# Player.net
KiCad netlist of a schematic drawn in EAGLE
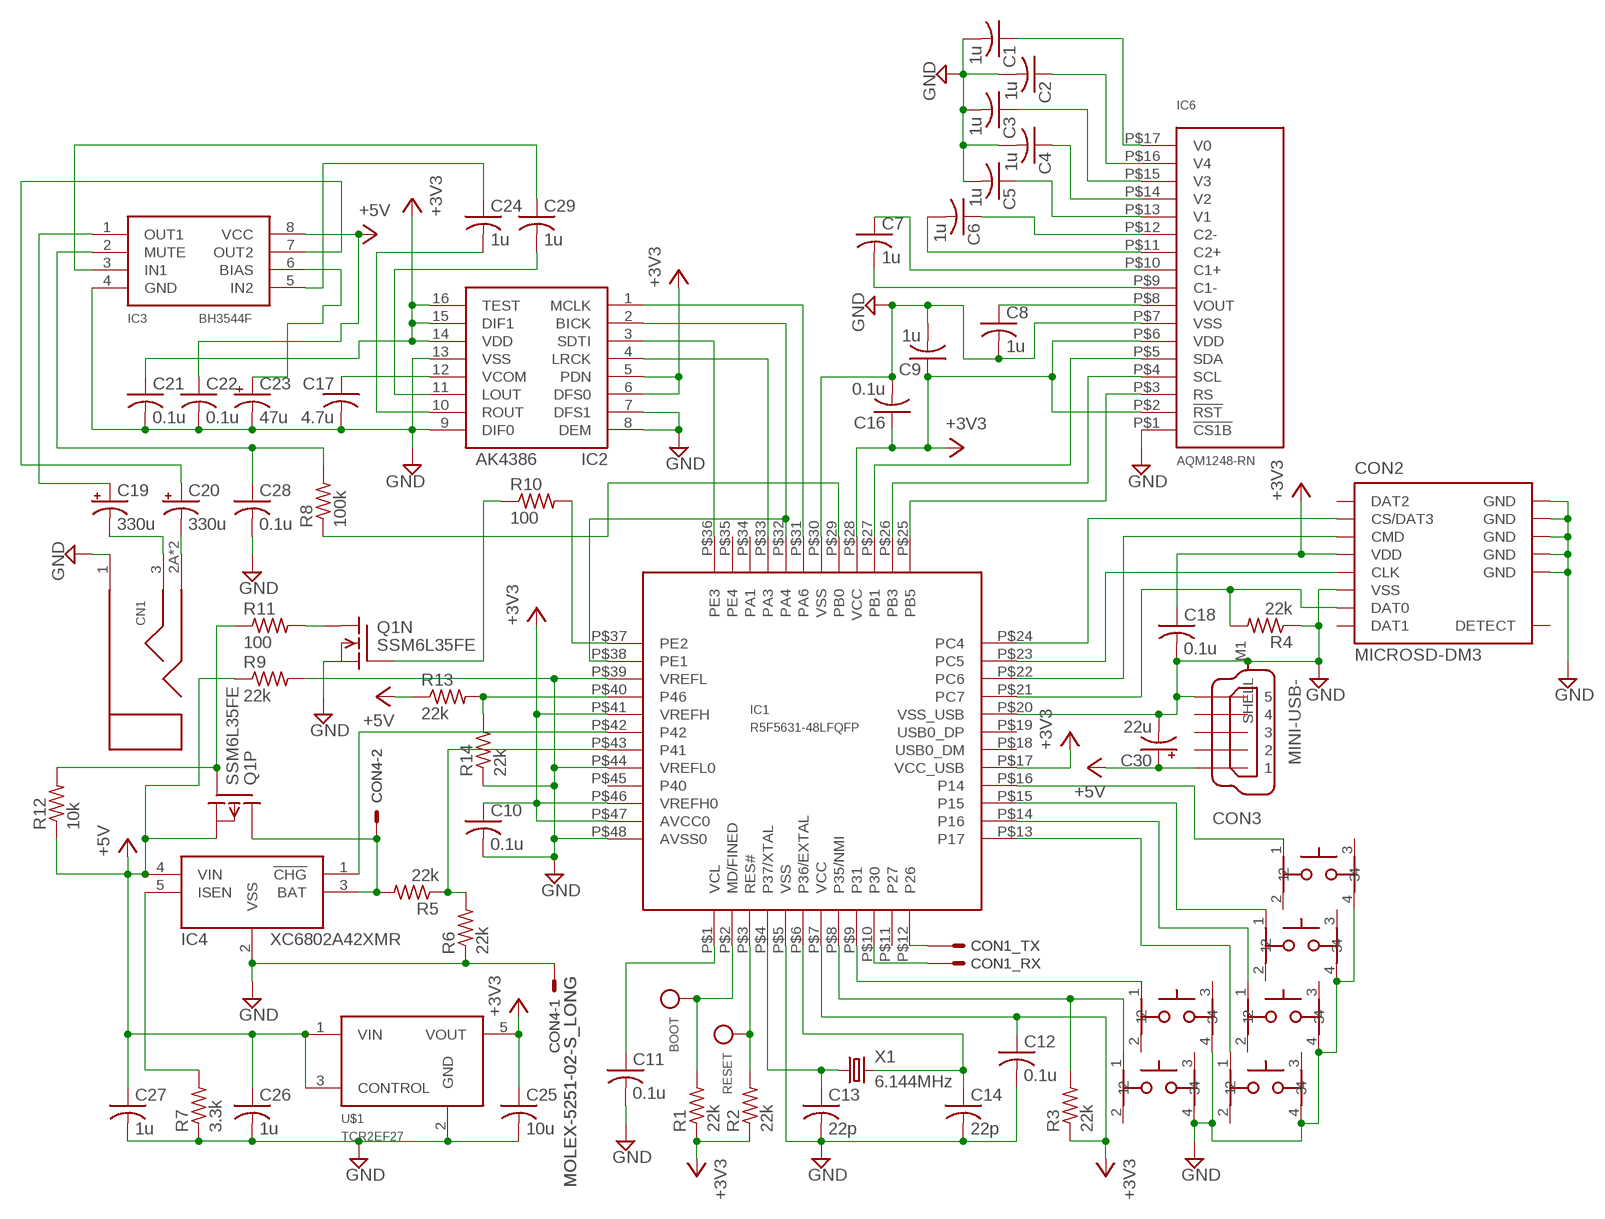
[diagram p0: schematic, sheet 1]

(export (version "E")
  (design (tool "Eeschema 10.0.6"))
  (components
    (comp (ref "BOOT")
      (value "CHECK_PIN")
      (footprint "eagle-import:SLC-22-G")
      (libsource (lib "eagle-import") (part "CHECK_PIN"))
    )
    (comp (ref "C1")
      (value "1u")
      (footprint "eagle-import:2012-C")
      (libsource (lib "eagle-import") (part "C-2012"))
    )
    (comp (ref "C2")
      (value "1u")
      (footprint "eagle-import:2012-C")
      (libsource (lib "eagle-import") (part "C-2012"))
    )
    (comp (ref "C3")
      (value "1u")
      (footprint "eagle-import:2012-C")
      (libsource (lib "eagle-import") (part "C-2012"))
    )
    (comp (ref "C4")
      (value "1u")
      (footprint "eagle-import:2012-C")
      (libsource (lib "eagle-import") (part "C-2012"))
    )
    (comp (ref "C5")
      (value "1u")
      (footprint "eagle-import:2012-C")
      (libsource (lib "eagle-import") (part "C-2012"))
    )
    (comp (ref "C6")
      (value "1u")
      (footprint "eagle-import:2012-C")
      (libsource (lib "eagle-import") (part "C-2012"))
    )
    (comp (ref "C7")
      (value "1u")
      (footprint "eagle-import:2012-C")
      (libsource (lib "eagle-import") (part "C-2012"))
    )
    (comp (ref "C8")
      (value "1u")
      (footprint "eagle-import:2012-C")
      (libsource (lib "eagle-import") (part "C-2012"))
    )
    (comp (ref "C9")
      (value "1u")
      (footprint "eagle-import:2012-C")
      (libsource (lib "eagle-import") (part "C-2012"))
    )
    (comp (ref "C10")
      (value "0.1u")
      (footprint "eagle-import:2012-C")
      (libsource (lib "eagle-import") (part "C-2012"))
    )
    (comp (ref "C11")
      (value "0.1u")
      (footprint "eagle-import:2012-C")
      (libsource (lib "eagle-import") (part "C-2012"))
    )
    (comp (ref "C12")
      (value "0.1u")
      (footprint "eagle-import:2012-C")
      (libsource (lib "eagle-import") (part "C-2012"))
    )
    (comp (ref "C13")
      (value "22p")
      (footprint "eagle-import:1608")
      (libsource (lib "eagle-import") (part "C-1608"))
    )
    (comp (ref "C14")
      (value "22p")
      (footprint "eagle-import:1608")
      (libsource (lib "eagle-import") (part "C-1608"))
    )
    (comp (ref "C16")
      (value "0.1u")
      (footprint "eagle-import:2012-C")
      (libsource (lib "eagle-import") (part "C-2012"))
    )
    (comp (ref "C17")
      (value "4.7u")
      (footprint "eagle-import:2012-C")
      (libsource (lib "eagle-import") (part "C-2012"))
    )
    (comp (ref "C18")
      (value "0.1u")
      (footprint "eagle-import:2012-C")
      (libsource (lib "eagle-import") (part "C-2012"))
    )
    (comp (ref "C19")
      (value "330u")
      (footprint "eagle-import:E2,5-8")
      (libsource (lib "eagle-import") (part "CC-2.5-8"))
    )
    (comp (ref "C20")
      (value "330u")
      (footprint "eagle-import:E2,5-8")
      (libsource (lib "eagle-import") (part "CC-2.5-8"))
    )
    (comp (ref "C21")
      (value "0.1u")
      (footprint "eagle-import:2012-C")
      (libsource (lib "eagle-import") (part "C-2012"))
    )
    (comp (ref "C22")
      (value "0.1u")
      (footprint "eagle-import:2012-C")
      (libsource (lib "eagle-import") (part "C-2012"))
    )
    (comp (ref "C23")
      (value "47u")
      (footprint "eagle-import:E2,5-8")
      (libsource (lib "eagle-import") (part "CC-2.5-8"))
    )
    (comp (ref "C24")
      (value "1u")
      (footprint "eagle-import:2012-C")
      (libsource (lib "eagle-import") (part "C-2012"))
    )
    (comp (ref "C25")
      (value "10u")
      (footprint "eagle-import:3216")
      (libsource (lib "eagle-import") (part "C-3216"))
    )
    (comp (ref "C26")
      (value "1u")
      (footprint "eagle-import:2012-C")
      (libsource (lib "eagle-import") (part "C-2012"))
    )
    (comp (ref "C27")
      (value "1u")
      (footprint "eagle-import:2012-C")
      (libsource (lib "eagle-import") (part "C-2012"))
    )
    (comp (ref "C28")
      (value "0.1u")
      (footprint "eagle-import:2012-C")
      (libsource (lib "eagle-import") (part "C-2012"))
    )
    (comp (ref "C29")
      (value "1u")
      (footprint "eagle-import:2012-C")
      (libsource (lib "eagle-import") (part "C-2012"))
    )
    (comp (ref "C30")
      (value "22u")
      (footprint "eagle-import:E2,5-8")
      (libsource (lib "eagle-import") (part "CC-2.5-8"))
    )
    (comp (ref "CN1")
      (value "STEREO-3.5-MJ8435")
      (footprint "eagle-import:MJ8435")
      (libsource (lib "eagle-import") (part "STEREO-3.5-MJ8435"))
    )
    (comp (ref "CON1")
      (value "UART-S")
      (footprint "eagle-import:IL-G-04-S")
      (libsource (lib "eagle-import") (part "UART-S"))
    )
    (comp (ref "CON2")
      (value "MICROSD-DM3")
      (footprint "eagle-import:DM3AT-SF-PEJ")
      (libsource (lib "eagle-import") (part "MICROSD-DM3"))
    )
    (comp (ref "CON3")
      (value "MINI-USB-")
      (footprint "eagle-import:UX60A-MB-5ST")
      (libsource (lib "eagle-import") (part "MINI-USB-"))
    )
    (comp (ref "CON4")
      (value "MOLEX-5251-02-S_LONG")
      (footprint "eagle-import:5251-02-S_LONG")
      (libsource (lib "eagle-import") (part "MOLEX-5251-02-S_LONG"))
    )
    (comp (ref "IC1")
      (value "R5F5631-48LFQFP")
      (footprint "eagle-import:P-LFQFP48-7X7-0.50")
      (libsource (lib "eagle-import") (part "R5F5631-48LFQFP"))
    )
    (comp (ref "IC2")
      (value "AK4386")
      (footprint "eagle-import:TSSOP16")
      (libsource (lib "eagle-import") (part "AK4386"))
    )
    (comp (ref "IC3")
      (value "BH3544F")
      (footprint "eagle-import:SOIC8")
      (libsource (lib "eagle-import") (part "BH3544F"))
    )
    (comp (ref "IC4")
      (value "XC6802A42XMR")
      (footprint "eagle-import:SOT23-5")
      (libsource (lib "eagle-import") (part "XC6802A42XMR"))
    )
    (comp (ref "IC6")
      (value "AQM1248-RN")
      (footprint "eagle-import:AQM1248A-RN")
      (libsource (lib "eagle-import") (part "AQM1248-RN"))
    )
    (comp (ref "Q1")
      (value "SSM6L35FE")
      (footprint "eagle-import:2-2N1D")
      (libsource (lib "eagle-import") (part "SSM6L35FE"))
    )
    (comp (ref "R1")
      (value "22k")
      (footprint "eagle-import:2012-R")
      (libsource (lib "eagle-import") (part "R-2012"))
    )
    (comp (ref "R2")
      (value "22k")
      (footprint "eagle-import:2012-R")
      (libsource (lib "eagle-import") (part "R-2012"))
    )
    (comp (ref "R3")
      (value "22k")
      (footprint "eagle-import:2012-R")
      (libsource (lib "eagle-import") (part "R-2012"))
    )
    (comp (ref "R4")
      (value "22k")
      (footprint "eagle-import:2012-R")
      (libsource (lib "eagle-import") (part "R-2012"))
    )
    (comp (ref "R5")
      (value "22k")
      (footprint "eagle-import:2012-R")
      (libsource (lib "eagle-import") (part "R-2012"))
    )
    (comp (ref "R6")
      (value "22k")
      (footprint "eagle-import:2012-R")
      (libsource (lib "eagle-import") (part "R-2012"))
    )
    (comp (ref "R7")
      (value "3.3k")
      (footprint "eagle-import:2012-R")
      (libsource (lib "eagle-import") (part "R-2012"))
    )
    (comp (ref "R8")
      (value "100k")
      (footprint "eagle-import:2012-R")
      (libsource (lib "eagle-import") (part "R-2012"))
    )
    (comp (ref "R9")
      (value "22k")
      (footprint "eagle-import:2012-R")
      (libsource (lib "eagle-import") (part "R-2012"))
    )
    (comp (ref "R10")
      (value "100")
      (footprint "eagle-import:2012-R")
      (libsource (lib "eagle-import") (part "R-2012"))
    )
    (comp (ref "R11")
      (value "100")
      (footprint "eagle-import:2012-R")
      (libsource (lib "eagle-import") (part "R-2012"))
    )
    (comp (ref "R12")
      (value "10k")
      (footprint "eagle-import:2012-R")
      (libsource (lib "eagle-import") (part "R-2012"))
    )
    (comp (ref "R13")
      (value "22k")
      (footprint "eagle-import:2012-R")
      (libsource (lib "eagle-import") (part "R-2012"))
    )
    (comp (ref "R14")
      (value "22k")
      (footprint "eagle-import:2012-R")
      (libsource (lib "eagle-import") (part "R-2012"))
    )
    (comp (ref "RESET")
      (value "CHECK_PIN")
      (footprint "eagle-import:SLC-22-G")
      (libsource (lib "eagle-import") (part "CHECK_PIN"))
    )
    (comp (ref "SW1")
      (value "PUSHSW")
      (footprint "eagle-import:PUSHSW")
      (libsource (lib "eagle-import") (part "PUSHSW"))
    )
    (comp (ref "SW2")
      (value "PUSHSW")
      (footprint "eagle-import:PUSHSW")
      (libsource (lib "eagle-import") (part "PUSHSW"))
    )
    (comp (ref "SW3")
      (value "PUSHSW")
      (footprint "eagle-import:PUSHSW")
      (libsource (lib "eagle-import") (part "PUSHSW"))
    )
    (comp (ref "SW4")
      (value "PUSHSW")
      (footprint "eagle-import:PUSHSW")
      (libsource (lib "eagle-import") (part "PUSHSW"))
    )
    (comp (ref "SW5")
      (value "PUSHSW")
      (footprint "eagle-import:PUSHSW")
      (libsource (lib "eagle-import") (part "PUSHSW"))
    )
    (comp (ref "SW6")
      (value "PUSHSW")
      (footprint "eagle-import:PUSHSW")
      (libsource (lib "eagle-import") (part "PUSHSW"))
    )
    (comp (ref "U$1")
      (value "TCR2EF27")
      (footprint "eagle-import:5-LEAD_TSOT")
      (libsource (lib "eagle-import") (part "TCR2EF"))
    )
    (comp (ref "X1")
      (value "6.144MHz")
      (footprint "eagle-import:TINYCRYSTAL")
      (libsource (lib "eagle-import") (part "CRYSTALTINY"))
    )
  )
  (nets
    (net (code "1") (name "+3V3") (class "Default")
      (node (ref "C10") (pin "1") (pinfunction "1_1") (pintype "passive"))
      (node (ref "C12") (pin "1") (pinfunction "1_1") (pintype "passive"))
      (node (ref "C16") (pin "1") (pinfunction "1_1") (pintype "passive"))
      (node (ref "C18") (pin "1") (pinfunction "1_1") (pintype "passive"))
      (node (ref "C21") (pin "1") (pinfunction "1_1") (pintype "passive"))
      (node (ref "C25") (pin "1") (pinfunction "1_1") (pintype "passive"))
      (node (ref "C9") (pin "1") (pinfunction "1_1") (pintype "passive"))
      (node (ref "CON2") (pin "4") (pinfunction "VDD_4") (pintype "power_in"))
      (node (ref "IC1") (pin "P$17") (pinfunction "VCC_USB_P$17") (pintype "power_in"))
      (node (ref "IC1") (pin "P$28") (pinfunction "VCC_P$28") (pintype "power_in"))
      (node (ref "IC1") (pin "P$41") (pinfunction "VREFH_P$41") (pintype "passive"))
      (node (ref "IC1") (pin "P$46") (pinfunction "VREFH0_P$46") (pintype "passive"))
      (node (ref "IC1") (pin "P$47") (pinfunction "AVCC0_P$47") (pintype "power_in"))
      (node (ref "IC1") (pin "P$7") (pinfunction "VCC_P$7") (pintype "power_in"))
      (node (ref "IC2") (pin "14") (pinfunction "VDD_14") (pintype "bidirectional"))
      (node (ref "IC2") (pin "15") (pinfunction "DIF1_15") (pintype "bidirectional"))
      (node (ref "IC2") (pin "16") (pinfunction "TEST_16") (pintype "bidirectional"))
      (node (ref "IC2") (pin "5") (pinfunction "PDN_5") (pintype "bidirectional"))
      (node (ref "IC2") (pin "6") (pinfunction "DFS0_6") (pintype "bidirectional"))
      (node (ref "IC6") (pin "P$2") (pinfunction "~{RST}_P$2") (pintype "bidirectional"))
      (node (ref "IC6") (pin "P$6") (pinfunction "VDD_P$6") (pintype "bidirectional"))
      (node (ref "R1") (pin "1") (pinfunction "1_1") (pintype "passive"))
      (node (ref "R2") (pin "1") (pinfunction "1_1") (pintype "passive"))
      (node (ref "R3") (pin "1") (pinfunction "1_1") (pintype "passive"))
      (node (ref "U$1") (pin "5") (pinfunction "VOUT_5") (pintype "bidirectional"))
    )
    (net (code "2") (name "+5V") (class "Default")
      (node (ref "C22") (pin "1") (pinfunction "1_1") (pintype "passive"))
      (node (ref "C26") (pin "1") (pinfunction "1_1") (pintype "passive"))
      (node (ref "C27") (pin "1") (pinfunction "1_1") (pintype "passive"))
      (node (ref "C30") (pin "+") (pinfunction "+_+") (pintype "passive"))
      (node (ref "CON3") (pin "1") (pinfunction "1_1") (pintype "input"))
      (node (ref "IC3") (pin "8") (pinfunction "VCC_8") (pintype "bidirectional"))
      (node (ref "IC4") (pin "4") (pinfunction "VIN_4") (pintype "power_in"))
      (node (ref "Q1") (pin "4") (pinfunction "S_4") (pintype "passive"))
      (node (ref "R12") (pin "1") (pinfunction "1_1") (pintype "passive"))
      (node (ref "R13") (pin "1") (pinfunction "1_1") (pintype "passive"))
      (node (ref "R9") (pin "1") (pinfunction "1_1") (pintype "passive"))
      (node (ref "U$1") (pin "1") (pinfunction "VIN_1") (pintype "bidirectional"))
      (node (ref "U$1") (pin "3") (pinfunction "CONTROL_3") (pintype "bidirectional"))
    )
    (net (code "3") (name "GND") (class "Default")
      (node (ref "C1") (pin "2") (pinfunction "2_2") (pintype "passive"))
      (node (ref "C10") (pin "2") (pinfunction "2_2") (pintype "passive"))
      (node (ref "C11") (pin "2") (pinfunction "2_2") (pintype "passive"))
      (node (ref "C12") (pin "2") (pinfunction "2_2") (pintype "passive"))
      (node (ref "C13") (pin "2") (pinfunction "2_2") (pintype "passive"))
      (node (ref "C14") (pin "2") (pinfunction "2_2") (pintype "passive"))
      (node (ref "C16") (pin "2") (pinfunction "2_2") (pintype "passive"))
      (node (ref "C17") (pin "2") (pinfunction "2_2") (pintype "passive"))
      (node (ref "C18") (pin "2") (pinfunction "2_2") (pintype "passive"))
      (node (ref "C2") (pin "2") (pinfunction "2_2") (pintype "passive"))
      (node (ref "C21") (pin "2") (pinfunction "2_2") (pintype "passive"))
      (node (ref "C22") (pin "2") (pinfunction "2_2") (pintype "passive"))
      (node (ref "C23") (pin "-") (pinfunction "-_-") (pintype "passive"))
      (node (ref "C25") (pin "2") (pinfunction "2_2") (pintype "passive"))
      (node (ref "C26") (pin "2") (pinfunction "2_2") (pintype "passive"))
      (node (ref "C27") (pin "2") (pinfunction "2_2") (pintype "passive"))
      (node (ref "C28") (pin "2") (pinfunction "2_2") (pintype "passive"))
      (node (ref "C3") (pin "2") (pinfunction "2_2") (pintype "passive"))
      (node (ref "C30") (pin "-") (pinfunction "-_-") (pintype "passive"))
      (node (ref "C4") (pin "2") (pinfunction "2_2") (pintype "passive"))
      (node (ref "C5") (pin "2") (pinfunction "2_2") (pintype "passive"))
      (node (ref "C8") (pin "2") (pinfunction "2_2") (pintype "passive"))
      (node (ref "C9") (pin "2") (pinfunction "2_2") (pintype "passive"))
      (node (ref "CN1") (pin "1") (pinfunction "SLEEVE_1") (pintype "passive"))
      (node (ref "CON2") (pin "6") (pinfunction "VSS_6") (pintype "power_in"))
      (node (ref "CON2") (pin "SHELL1") (pinfunction "GND_SHELL1") (pintype "power_in"))
      (node (ref "CON2") (pin "SHELL2") (pinfunction "GND_SHELL2") (pintype "power_in"))
      (node (ref "CON2") (pin "SHELL3") (pinfunction "GND_SHELL3") (pintype "power_in"))
      (node (ref "CON2") (pin "SHELL4") (pinfunction "GND_SHELL4") (pintype "power_in"))
      (node (ref "CON2") (pin "SHELL5") (pinfunction "GND_SHELL5") (pintype "power_in"))
      (node (ref "CON3") (pin "5") (pinfunction "5_5") (pintype "input"))
      (node (ref "CON3") (pin "M1") (pinfunction "SHELL_M1") (pintype "bidirectional"))
      (node (ref "CON4") (pin "1") (pinfunction "S_1") (pintype "passive"))
      (node (ref "IC1") (pin "P$20") (pinfunction "VSS_USB_P$20") (pintype "power_in"))
      (node (ref "IC1") (pin "P$30") (pinfunction "VSS_P$30") (pintype "power_in"))
      (node (ref "IC1") (pin "P$39") (pinfunction "VREFL_P$39") (pintype "passive"))
      (node (ref "IC1") (pin "P$44") (pinfunction "VREFL0_P$44") (pintype "passive"))
      (node (ref "IC1") (pin "P$48") (pinfunction "AVSS0_P$48") (pintype "power_in"))
      (node (ref "IC1") (pin "P$5") (pinfunction "VSS_P$5") (pintype "power_in"))
      (node (ref "IC2") (pin "13") (pinfunction "VSS_13") (pintype "bidirectional"))
      (node (ref "IC2") (pin "7") (pinfunction "DFS1_7") (pintype "bidirectional"))
      (node (ref "IC2") (pin "8") (pinfunction "DEM_8") (pintype "bidirectional"))
      (node (ref "IC2") (pin "9") (pinfunction "DIF0_9") (pintype "bidirectional"))
      (node (ref "IC3") (pin "4") (pinfunction "GND_4") (pintype "bidirectional"))
      (node (ref "IC4") (pin "2") (pinfunction "VSS_2") (pintype "power_in"))
      (node (ref "IC6") (pin "P$1") (pinfunction "~{CS1B}_P$1") (pintype "bidirectional"))
      (node (ref "IC6") (pin "P$7") (pinfunction "VSS_P$7") (pintype "bidirectional"))
      (node (ref "Q1") (pin "1") (pinfunction "S_1") (pintype "passive"))
      (node (ref "R14") (pin "1") (pinfunction "1_1") (pintype "passive"))
      (node (ref "R4") (pin "1") (pinfunction "1_1") (pintype "passive"))
      (node (ref "R6") (pin "1") (pinfunction "1_1") (pintype "passive"))
      (node (ref "R7") (pin "1") (pinfunction "1_1") (pintype "passive"))
      (node (ref "R9") (pin "2") (pinfunction "2_2") (pintype "passive"))
      (node (ref "SW1") (pin "4") (pinfunction "4_4") (pintype "bidirectional"))
      (node (ref "SW2") (pin "4") (pinfunction "4_4") (pintype "bidirectional"))
      (node (ref "SW3") (pin "4") (pinfunction "4_4") (pintype "bidirectional"))
      (node (ref "SW4") (pin "4") (pinfunction "4_4") (pintype "bidirectional"))
      (node (ref "SW5") (pin "4") (pinfunction "4_4") (pintype "bidirectional"))
      (node (ref "SW6") (pin "4") (pinfunction "4_4") (pintype "bidirectional"))
      (node (ref "U$1") (pin "2") (pinfunction "GND_2") (pintype "bidirectional"))
    )
    (net (code "4") (name "Net-(C20-Pad-)") (class "Default")
      (node (ref "C20") (pin "-") (pinfunction "-_-") (pintype "passive"))
      (node (ref "CN1") (pin "2A") (pinfunction "TIP_2A") (pintype "passive"))
      (node (ref "CN1") (pin "2B") (pinfunction "TIP_2B") (pintype "passive"))
    )
    (net (code "5") (name "Net-(CN1-RING)") (class "Default")
      (node (ref "C19") (pin "-") (pinfunction "-_-") (pintype "passive"))
      (node (ref "CN1") (pin "3") (pinfunction "RING_3") (pintype "passive"))
    )
    (net (code "6") (name "Net-(CON1B-S)") (class "Default")
      (node (ref "CON1") (pin "2") (pinfunction "S_2") (pintype "passive"))
      (node (ref "IC1") (pin "P$10") (pinfunction "P30_P$10") (pintype "bidirectional"))
    )
    (net (code "7") (name "Net-(CON1C-S)") (class "Default")
      (node (ref "CON1") (pin "3") (pinfunction "S_3") (pintype "passive"))
      (node (ref "IC1") (pin "P$12") (pinfunction "P26_P$12") (pintype "bidirectional"))
    )
    (net (code "8") (name "Net-(CON2-CLK)") (class "Default")
      (node (ref "CON2") (pin "5") (pinfunction "CLK_5") (pintype "input"))
      (node (ref "IC1") (pin "P$23") (pinfunction "PC5_P$23") (pintype "bidirectional"))
    )
    (net (code "9") (name "Net-(CON2-CMD)") (class "Default")
      (node (ref "CON2") (pin "3") (pinfunction "CMD_3") (pintype "input"))
      (node (ref "IC1") (pin "P$22") (pinfunction "PC6_P$22") (pintype "bidirectional"))
    )
    (net (code "10") (name "Net-(CON2-CS{slash}DAT3)") (class "Default")
      (node (ref "CON2") (pin "2") (pinfunction "CS/DAT3_2") (pintype "input"))
      (node (ref "IC1") (pin "P$24") (pinfunction "PC4_P$24") (pintype "bidirectional"))
    )
    (net (code "11") (name "Net-(CON2-DAT0)") (class "Default")
      (node (ref "CON2") (pin "7") (pinfunction "DAT0_7") (pintype "bidirectional"))
      (node (ref "IC1") (pin "P$21") (pinfunction "PC7_P$21") (pintype "bidirectional"))
      (node (ref "R4") (pin "2") (pinfunction "2_2") (pintype "passive"))
    )
    (net (code "12") (name "Net-(CON4B-S)") (class "Default")
      (node (ref "CON4") (pin "2") (pinfunction "S_2") (pintype "passive"))
      (node (ref "IC4") (pin "3") (pinfunction "BAT_3") (pintype "passive"))
      (node (ref "Q1") (pin "3") (pinfunction "D_3") (pintype "passive"))
      (node (ref "R5") (pin "2") (pinfunction "2_2") (pintype "passive"))
    )
    (net (code "13") (name "Net-(IC1-MD{slash}FINED)") (class "Default")
      (node (ref "BOOT") (pin "SIGNAL") (pinfunction "SIGNAL_SIGNAL") (pintype "bidirectional"))
      (node (ref "IC1") (pin "P$2") (pinfunction "MD/FINED_P$2") (pintype "input"))
      (node (ref "R1") (pin "2") (pinfunction "2_2") (pintype "passive"))
    )
    (net (code "14") (name "Net-(IC1-P14)") (class "Default")
      (node (ref "IC1") (pin "P$16") (pinfunction "P14_P$16") (pintype "bidirectional"))
      (node (ref "SW6") (pin "1") (pinfunction "1_1") (pintype "bidirectional"))
    )
    (net (code "15") (name "Net-(IC1-P15)") (class "Default")
      (node (ref "IC1") (pin "P$15") (pinfunction "P15_P$15") (pintype "bidirectional"))
      (node (ref "SW5") (pin "1") (pinfunction "1_1") (pintype "bidirectional"))
    )
    (net (code "16") (name "Net-(IC1-P16)") (class "Default")
      (node (ref "IC1") (pin "P$14") (pinfunction "P16_P$14") (pintype "bidirectional"))
      (node (ref "SW4") (pin "1") (pinfunction "1_1") (pintype "bidirectional"))
    )
    (net (code "17") (name "Net-(IC1-P17)") (class "Default")
      (node (ref "IC1") (pin "P$13") (pinfunction "P17_P$13") (pintype "bidirectional"))
      (node (ref "SW3") (pin "1") (pinfunction "1_1") (pintype "bidirectional"))
    )
    (net (code "18") (name "Net-(IC1-P31)") (class "Default")
      (node (ref "IC1") (pin "P$9") (pinfunction "P31_P$9") (pintype "bidirectional"))
      (node (ref "SW2") (pin "1") (pinfunction "1_1") (pintype "bidirectional"))
    )
    (net (code "19") (name "Net-(IC1-P35{slash}NMI)") (class "Default")
      (node (ref "IC1") (pin "P$8") (pinfunction "P35/NMI_P$8") (pintype "input"))
      (node (ref "R3") (pin "2") (pinfunction "2_2") (pintype "passive"))
      (node (ref "SW1") (pin "1") (pinfunction "1_1") (pintype "bidirectional"))
    )
    (net (code "20") (name "Net-(IC1-P36{slash}EXTAL)") (class "Default")
      (node (ref "C14") (pin "1") (pinfunction "1_1") (pintype "passive"))
      (node (ref "IC1") (pin "P$6") (pinfunction "P36/EXTAL_P$6") (pintype "bidirectional"))
      (node (ref "X1") (pin "2") (pinfunction "2_2") (pintype "passive"))
    )
    (net (code "21") (name "Net-(IC1-P37{slash}XTAL)") (class "Default")
      (node (ref "C13") (pin "1") (pinfunction "1_1") (pintype "passive"))
      (node (ref "IC1") (pin "P$4") (pinfunction "P37/XTAL_P$4") (pintype "bidirectional"))
      (node (ref "X1") (pin "1") (pinfunction "1_1") (pintype "passive"))
    )
    (net (code "22") (name "Net-(IC1-P41)") (class "Default")
      (node (ref "IC1") (pin "P$43") (pinfunction "P41_P$43") (pintype "bidirectional"))
      (node (ref "R5") (pin "1") (pinfunction "1_1") (pintype "passive"))
      (node (ref "R6") (pin "2") (pinfunction "2_2") (pintype "passive"))
    )
    (net (code "23") (name "Net-(IC1-P42)") (class "Default")
      (node (ref "IC1") (pin "P$42") (pinfunction "P42_P$42") (pintype "bidirectional"))
      (node (ref "IC4") (pin "1") (pinfunction "~{CHG}_1") (pintype "open_collector"))
    )
    (net (code "24") (name "Net-(IC1-P46)") (class "Default")
      (node (ref "IC1") (pin "P$40") (pinfunction "P46_P$40") (pintype "bidirectional"))
      (node (ref "R13") (pin "2") (pinfunction "2_2") (pintype "passive"))
      (node (ref "R14") (pin "2") (pinfunction "2_2") (pintype "passive"))
    )
    (net (code "25") (name "Net-(IC1-PA3)") (class "Default")
      (node (ref "IC1") (pin "P$33") (pinfunction "PA3_P$33") (pintype "bidirectional"))
      (node (ref "IC2") (pin "4") (pinfunction "LRCK_4") (pintype "bidirectional"))
    )
    (net (code "26") (name "Net-(IC1-PA4)") (class "Default")
      (node (ref "IC1") (pin "P$32") (pinfunction "PA4_P$32") (pintype "bidirectional"))
      (node (ref "IC1") (pin "P$38") (pinfunction "PE1_P$38") (pintype "bidirectional"))
      (node (ref "IC2") (pin "2") (pinfunction "BICK_2") (pintype "bidirectional"))
    )
    (net (code "27") (name "Net-(IC1-PA6)") (class "Default")
      (node (ref "IC1") (pin "P$31") (pinfunction "PA6_P$31") (pintype "bidirectional"))
      (node (ref "IC2") (pin "1") (pinfunction "MCLK_1") (pintype "bidirectional"))
    )
    (net (code "28") (name "Net-(IC1-PB0)") (class "Default")
      (node (ref "IC1") (pin "P$29") (pinfunction "PB0_P$29") (pintype "bidirectional"))
      (node (ref "R8") (pin "1") (pinfunction "1_1") (pintype "passive"))
    )
    (net (code "29") (name "Net-(IC1-PB1)") (class "Default")
      (node (ref "IC1") (pin "P$27") (pinfunction "PB1_P$27") (pintype "bidirectional"))
      (node (ref "IC6") (pin "P$5") (pinfunction "SDA_P$5") (pintype "bidirectional"))
    )
    (net (code "30") (name "Net-(IC1-PB3)") (class "Default")
      (node (ref "IC1") (pin "P$26") (pinfunction "PB3_P$26") (pintype "bidirectional"))
      (node (ref "IC6") (pin "P$4") (pinfunction "SCL_P$4") (pintype "bidirectional"))
    )
    (net (code "31") (name "Net-(IC1-PB5)") (class "Default")
      (node (ref "IC1") (pin "P$25") (pinfunction "PB5_P$25") (pintype "bidirectional"))
      (node (ref "IC6") (pin "P$3") (pinfunction "RS_P$3") (pintype "bidirectional"))
    )
    (net (code "32") (name "Net-(IC1-PE2)") (class "Default")
      (node (ref "IC1") (pin "P$37") (pinfunction "PE2_P$37") (pintype "bidirectional"))
      (node (ref "R10") (pin "2") (pinfunction "2_2") (pintype "passive"))
    )
    (net (code "33") (name "Net-(IC1-PE3)") (class "Default")
      (node (ref "IC1") (pin "P$36") (pinfunction "PE3_P$36") (pintype "bidirectional"))
      (node (ref "IC2") (pin "3") (pinfunction "SDTI_3") (pintype "bidirectional"))
    )
    (net (code "34") (name "Net-(IC1-RES#)") (class "Default")
      (node (ref "IC1") (pin "P$3") (pinfunction "RES#_P$3") (pintype "input"))
      (node (ref "R2") (pin "2") (pinfunction "2_2") (pintype "passive"))
      (node (ref "RESET") (pin "SIGNAL") (pinfunction "SIGNAL_SIGNAL") (pintype "bidirectional"))
    )
    (net (code "35") (name "Net-(IC1-VCL)") (class "Default")
      (node (ref "C11") (pin "1") (pinfunction "1_1") (pintype "passive"))
      (node (ref "IC1") (pin "P$1") (pinfunction "VCL_P$1") (pintype "passive"))
    )
    (net (code "36") (name "Net-(IC2-LOUT)") (class "Default")
      (node (ref "C29") (pin "2") (pinfunction "2_2") (pintype "passive"))
      (node (ref "IC2") (pin "11") (pinfunction "LOUT_11") (pintype "bidirectional"))
    )
    (net (code "37") (name "Net-(IC2-ROUT)") (class "Default")
      (node (ref "C24") (pin "2") (pinfunction "2_2") (pintype "passive"))
      (node (ref "IC2") (pin "10") (pinfunction "ROUT_10") (pintype "bidirectional"))
    )
    (net (code "38") (name "Net-(IC2-VCOM)") (class "Default")
      (node (ref "C17") (pin "1") (pinfunction "1_1") (pintype "passive"))
      (node (ref "IC2") (pin "12") (pinfunction "VCOM_12") (pintype "bidirectional"))
    )
    (net (code "39") (name "Net-(IC3-BIAS)") (class "Default")
      (node (ref "C23") (pin "+") (pinfunction "+_+") (pintype "passive"))
      (node (ref "IC3") (pin "6") (pinfunction "BIAS_6") (pintype "bidirectional"))
    )
    (net (code "40") (name "Net-(IC3-IN1)") (class "Default")
      (node (ref "C29") (pin "1") (pinfunction "1_1") (pintype "passive"))
      (node (ref "IC3") (pin "3") (pinfunction "IN1_3") (pintype "bidirectional"))
    )
    (net (code "41") (name "Net-(IC3-IN2)") (class "Default")
      (node (ref "C24") (pin "1") (pinfunction "1_1") (pintype "passive"))
      (node (ref "IC3") (pin "5") (pinfunction "IN2_5") (pintype "bidirectional"))
    )
    (net (code "42") (name "Net-(IC3-MUTE)") (class "Default")
      (node (ref "C28") (pin "1") (pinfunction "1_1") (pintype "passive"))
      (node (ref "IC3") (pin "2") (pinfunction "MUTE_2") (pintype "bidirectional"))
      (node (ref "R8") (pin "2") (pinfunction "2_2") (pintype "passive"))
    )
    (net (code "43") (name "Net-(IC3-OUT1)") (class "Default")
      (node (ref "C19") (pin "+") (pinfunction "+_+") (pintype "passive"))
      (node (ref "IC3") (pin "1") (pinfunction "OUT1_1") (pintype "bidirectional"))
    )
    (net (code "44") (name "Net-(IC3-OUT2)") (class "Default")
      (node (ref "C20") (pin "+") (pinfunction "+_+") (pintype "passive"))
      (node (ref "IC3") (pin "7") (pinfunction "OUT2_7") (pintype "bidirectional"))
    )
    (net (code "45") (name "Net-(IC4-ISEN)") (class "Default")
      (node (ref "IC4") (pin "5") (pinfunction "ISEN_5") (pintype "passive"))
      (node (ref "R7") (pin "2") (pinfunction "2_2") (pintype "passive"))
    )
    (net (code "46") (name "Net-(IC6-C1+)") (class "Default")
      (node (ref "C7") (pin "1") (pinfunction "1_1") (pintype "passive"))
      (node (ref "IC6") (pin "P$10") (pinfunction "C1+_P$10") (pintype "bidirectional"))
    )
    (net (code "47") (name "Net-(IC6-C1-)") (class "Default")
      (node (ref "C7") (pin "2") (pinfunction "2_2") (pintype "passive"))
      (node (ref "IC6") (pin "P$9") (pinfunction "C1-_P$9") (pintype "bidirectional"))
    )
    (net (code "48") (name "Net-(IC6-C2+)") (class "Default")
      (node (ref "C6") (pin "2") (pinfunction "2_2") (pintype "passive"))
      (node (ref "IC6") (pin "P$11") (pinfunction "C2+_P$11") (pintype "bidirectional"))
    )
    (net (code "49") (name "Net-(IC6-C2-)") (class "Default")
      (node (ref "C6") (pin "1") (pinfunction "1_1") (pintype "passive"))
      (node (ref "IC6") (pin "P$12") (pinfunction "C2-_P$12") (pintype "bidirectional"))
    )
    (net (code "50") (name "Net-(IC6-V0)") (class "Default")
      (node (ref "C1") (pin "1") (pinfunction "1_1") (pintype "passive"))
      (node (ref "IC6") (pin "P$17") (pinfunction "V0_P$17") (pintype "bidirectional"))
    )
    (net (code "51") (name "Net-(IC6-V1)") (class "Default")
      (node (ref "C5") (pin "1") (pinfunction "1_1") (pintype "passive"))
      (node (ref "IC6") (pin "P$13") (pinfunction "V1_P$13") (pintype "bidirectional"))
    )
    (net (code "52") (name "Net-(IC6-V2)") (class "Default")
      (node (ref "C4") (pin "1") (pinfunction "1_1") (pintype "passive"))
      (node (ref "IC6") (pin "P$14") (pinfunction "V2_P$14") (pintype "bidirectional"))
    )
    (net (code "53") (name "Net-(IC6-V3)") (class "Default")
      (node (ref "C3") (pin "1") (pinfunction "1_1") (pintype "passive"))
      (node (ref "IC6") (pin "P$15") (pinfunction "V3_P$15") (pintype "bidirectional"))
    )
    (net (code "54") (name "Net-(IC6-V4)") (class "Default")
      (node (ref "C2") (pin "1") (pinfunction "1_1") (pintype "passive"))
      (node (ref "IC6") (pin "P$16") (pinfunction "V4_P$16") (pintype "bidirectional"))
    )
    (net (code "55") (name "Net-(IC6-VOUT)") (class "Default")
      (node (ref "C8") (pin "1") (pinfunction "1_1") (pintype "passive"))
      (node (ref "IC6") (pin "P$8") (pinfunction "VOUT_P$8") (pintype "bidirectional"))
    )
    (net (code "56") (name "Net-(Q1A-D)") (class "Default")
      (node (ref "Q1") (pin "6") (pinfunction "D_6") (pintype "passive"))
      (node (ref "R11") (pin "2") (pinfunction "2_2") (pintype "passive"))
    )
    (net (code "57") (name "Net-(Q1A-G)") (class "Default")
      (node (ref "Q1") (pin "2") (pinfunction "G_2") (pintype "passive"))
      (node (ref "R10") (pin "1") (pinfunction "1_1") (pintype "passive"))
    )
    (net (code "58") (name "Net-(Q1B-G)") (class "Default")
      (node (ref "Q1") (pin "5") (pinfunction "G_5") (pintype "passive"))
      (node (ref "R11") (pin "1") (pinfunction "1_1") (pintype "passive"))
      (node (ref "R12") (pin "2") (pinfunction "2_2") (pintype "passive"))
    )
    (net (code "59") (name "unconnected-(CON2-DAT1-Pad8)") (class "Default")
      (node (ref "CON2") (pin "8") (pinfunction "DAT1_8") (pintype "bidirectional"))
    )
    (net (code "60") (name "unconnected-(CON2-DAT2-Pad1)") (class "Default")
      (node (ref "CON2") (pin "1") (pinfunction "DAT2_1") (pintype "bidirectional"))
    )
    (net (code "61") (name "unconnected-(CON2-PadDETECT)") (class "Default")
      (node (ref "CON2") (pin "DETECT") (pinfunction "DETECT_DETECT") (pintype "passive"))
    )
    (net (code "62") (name "unconnected-(CON3-Pad2)") (class "Default")
      (node (ref "CON3") (pin "2") (pinfunction "2_2") (pintype "input"))
    )
    (net (code "63") (name "unconnected-(CON3-Pad3)") (class "Default")
      (node (ref "CON3") (pin "3") (pinfunction "3_3") (pintype "input"))
    )
    (net (code "64") (name "unconnected-(CON3-Pad4)") (class "Default")
      (node (ref "CON3") (pin "4") (pinfunction "4_4") (pintype "input"))
    )
    (net (code "65") (name "unconnected-(IC1-P27-PadP$11)") (class "Default")
      (node (ref "IC1") (pin "P$11") (pinfunction "P27_P$11") (pintype "bidirectional"))
    )
    (net (code "66") (name "unconnected-(IC1-P40-PadP$45)") (class "Default")
      (node (ref "IC1") (pin "P$45") (pinfunction "P40_P$45") (pintype "bidirectional"))
    )
    (net (code "67") (name "unconnected-(IC1-PA1-PadP$34)") (class "Default")
      (node (ref "IC1") (pin "P$34") (pinfunction "PA1_P$34") (pintype "bidirectional"))
    )
    (net (code "68") (name "unconnected-(IC1-PE4-PadP$35)") (class "Default")
      (node (ref "IC1") (pin "P$35") (pinfunction "PE4_P$35") (pintype "bidirectional"))
    )
    (net (code "69") (name "unconnected-(IC1-USB0_DM-PadP$18)") (class "Default")
      (node (ref "IC1") (pin "P$18") (pinfunction "USB0_DM_P$18") (pintype "bidirectional"))
    )
    (net (code "70") (name "unconnected-(IC1-USB0_DP-PadP$19)") (class "Default")
      (node (ref "IC1") (pin "P$19") (pinfunction "USB0_DP_P$19") (pintype "bidirectional"))
    )
    (net (code "71") (name "unconnected-(SW1-Pad2)") (class "Default")
      (node (ref "SW1") (pin "2") (pinfunction "2_2") (pintype "bidirectional"))
    )
    (net (code "72") (name "unconnected-(SW1-Pad3)") (class "Default")
      (node (ref "SW1") (pin "3") (pinfunction "3_3") (pintype "bidirectional"))
    )
    (net (code "73") (name "unconnected-(SW2-Pad2)") (class "Default")
      (node (ref "SW2") (pin "2") (pinfunction "2_2") (pintype "bidirectional"))
    )
    (net (code "74") (name "unconnected-(SW2-Pad3)") (class "Default")
      (node (ref "SW2") (pin "3") (pinfunction "3_3") (pintype "bidirectional"))
    )
    (net (code "75") (name "unconnected-(SW3-Pad2)") (class "Default")
      (node (ref "SW3") (pin "2") (pinfunction "2_2") (pintype "bidirectional"))
    )
    (net (code "76") (name "unconnected-(SW3-Pad3)") (class "Default")
      (node (ref "SW3") (pin "3") (pinfunction "3_3") (pintype "bidirectional"))
    )
    (net (code "77") (name "unconnected-(SW4-Pad2)") (class "Default")
      (node (ref "SW4") (pin "2") (pinfunction "2_2") (pintype "bidirectional"))
    )
    (net (code "78") (name "unconnected-(SW4-Pad3)") (class "Default")
      (node (ref "SW4") (pin "3") (pinfunction "3_3") (pintype "bidirectional"))
    )
    (net (code "79") (name "unconnected-(SW5-Pad2)") (class "Default")
      (node (ref "SW5") (pin "2") (pinfunction "2_2") (pintype "bidirectional"))
    )
    (net (code "80") (name "unconnected-(SW5-Pad3)") (class "Default")
      (node (ref "SW5") (pin "3") (pinfunction "3_3") (pintype "bidirectional"))
    )
    (net (code "81") (name "unconnected-(SW6-Pad2)") (class "Default")
      (node (ref "SW6") (pin "2") (pinfunction "2_2") (pintype "bidirectional"))
    )
    (net (code "82") (name "unconnected-(SW6-Pad3)") (class "Default")
      (node (ref "SW6") (pin "3") (pinfunction "3_3") (pintype "bidirectional"))
    )
  )
)
